# Peripherals.net
KiCad netlist of a schematic drawn in Altium Designer
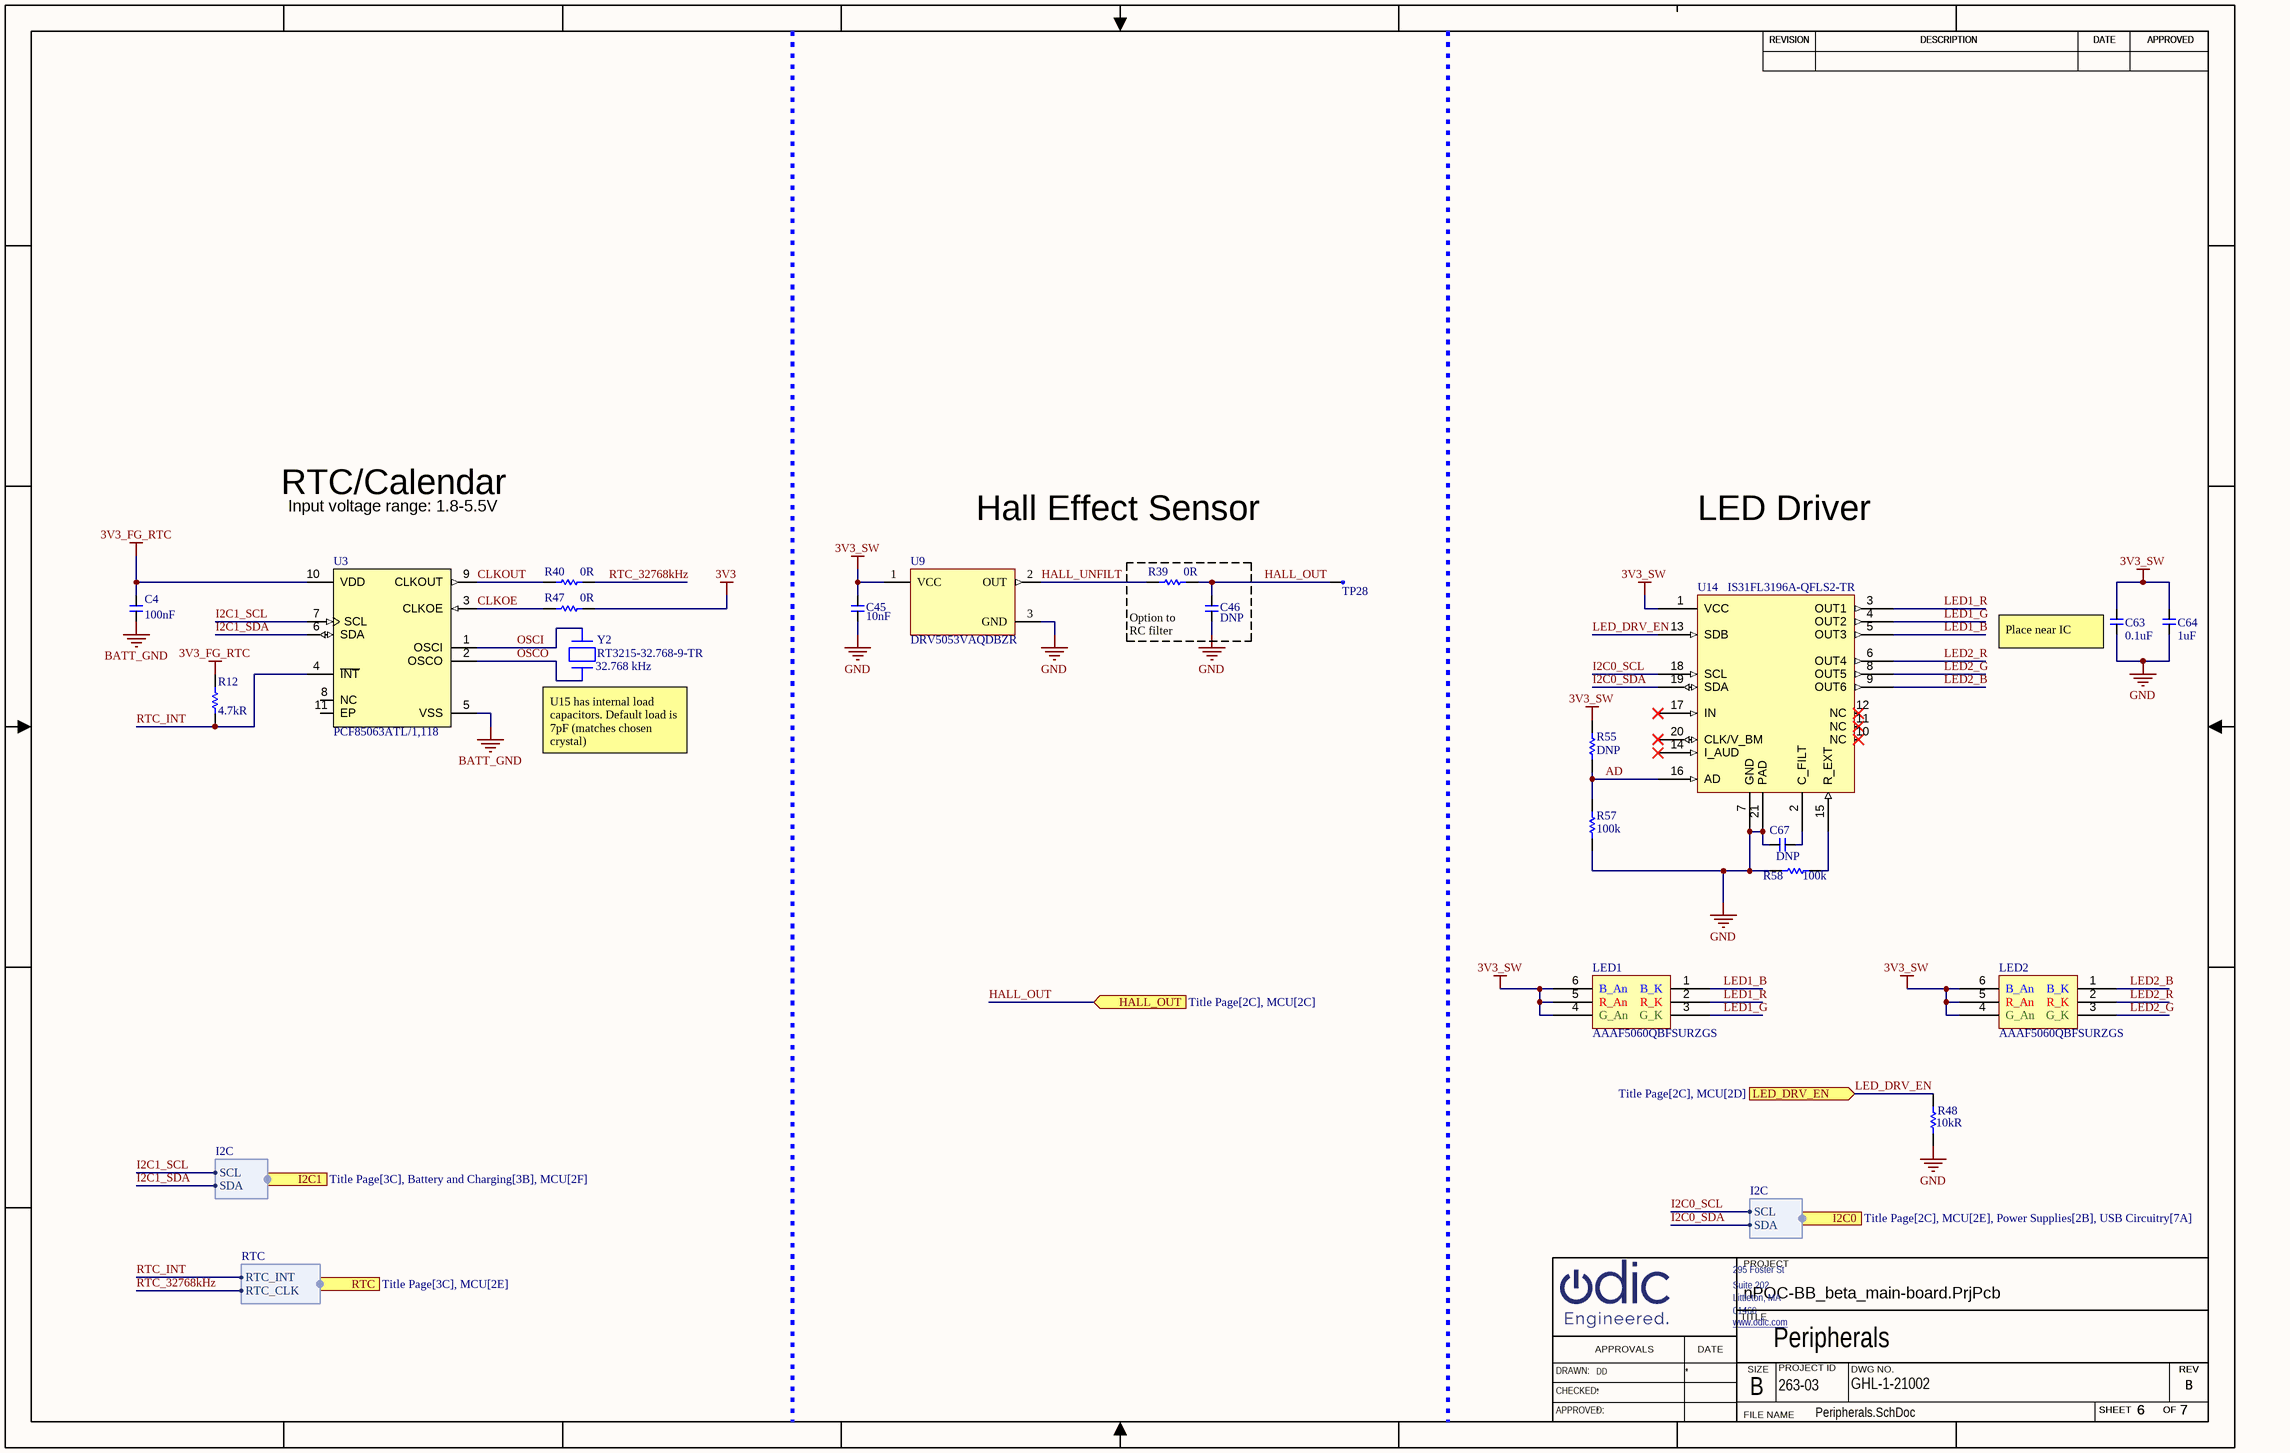
[diagram p0: Peripherals.SchDoc]

(export (version "E")
  (design (tool "Eeschema 10.0.6"))
  (components
    (comp (ref "C4")
      (value "C0402_100n_16V_10pct")
      (footprint "C0402")
      (description "0.1 µF ±10% 16V Ceramic Capacitor X7R 0402 (1005 Metric)")
      (fields
        (field (name "VOLTAGE") "16V")
        (field (name "TOLERANCE") "10%")
        (field (name "CAPACITANCE") "100nF")
      )
      (libsource (lib "Odic Inc") (part "cAP"))
    )
    (comp (ref "C45")
      (value "C0402_10n_6V3_10pct")
      (footprint "C0402")
      (description "CAP CER 10000PF 25V 10% X7R 0402")
      (fields
        (field (name "TOLERANCE") "10%")
        (field (name "CAPACITANCE") "10nF")
        (field (name "VOLTAGE") "25V")
      )
      (libsource (lib "Odic Inc") (part "cAP"))
    )
    (comp (ref "C46")
      (value "C0402 Footprint")
      (footprint "C0402")
      (description "Blank pads for future cap placements")
      (fields (field (name "INSTALL") "DNP"))
      (libsource (lib "Odic Inc") (part "cAP"))
    )
    (comp (ref "C63")
      (value "0.1uF")
      (footprint "C0402")
      (description "Cap Ceramic 0.1uF 25V X5R 10% Pad SMD 0402 Multi Layer Ceramic Capacitor (MLCC)")
      (fields (field (name "VOLTAGE") "25V") (field (name "TOLERANCE") "10%"))
      (libsource (lib "Odic Inc") (part "cAP"))
    )
    (comp (ref "C64")
      (value "1uF")
      (footprint "C0402")
      (description "CAP CER 1UF 16V X5R 0402")
      (fields (field (name "VOLTAGE") "16V") (field (name "TOLERANCE") "10%"))
      (libsource (lib "Odic Inc") (part "cAP"))
    )
    (comp (ref "C67")
      (value "N/A")
      (footprint "C0603")
      (description "DNP CAP")
      (fields
        (field (name "MANUFACTURER") "Samsung")
        (field (name "MANUFACTURER PART NUMBER") "CL10B104KB8NNWC")
        (field (name "INSTALL") "DNP")
      )
      (libsource (lib "Odic Inc") (part "cAP"))
    )
    (comp (ref "LED1")
      (value "AAAF5060QBFSURZGS")
      (footprint "led6_smt_5x6mm")
      (description "Blue/Red/Green 100º 400/800/1000 mcd Clear Surface Mount LED Lamp")
      (libsource (lib "Odic Inc") (part "AAAF5060QBFSURZGS-Symbol-1"))
    )
    (comp (ref "LED2")
      (value "AAAF5060QBFSURZGS")
      (footprint "led6_smt_5x6mm")
      (description "Blue/Red/Green 100º 400/800/1000 mcd Clear Surface Mount LED Lamp")
      (libsource (lib "Odic Inc") (part "AAAF5060QBFSURZGS-Symbol-1"))
    )
    (comp (ref "R12")
      (value "R0402_4k7_1pct")
      (footprint "R0402")
      (description "RES 4.7K OHM 1% 1/16W 0402")
      (fields (field (name "TOLERANCE") "1%") (field (name "RESISTANCE") "4.7kR"))
      (libsource (lib "Odic Inc") (part "RES"))
    )
    (comp (ref "R39")
      (value "R0402_0R")
      (footprint "R0402")
      (description "RES 0 OHM JUMPER 1/16W 0402")
      (fields (field (name "RESISTANCE") "0R"))
      (libsource (lib "Odic Inc") (part "RES"))
    )
    (comp (ref "R40")
      (value "R0402_0R")
      (footprint "R0402")
      (description "RES 0 OHM JUMPER 1/16W 0402")
      (fields (field (name "RESISTANCE") "0R"))
      (libsource (lib "Odic Inc") (part "RES"))
    )
    (comp (ref "R47")
      (value "R0402_0R")
      (footprint "R0402")
      (description "RES 0 OHM JUMPER 1/16W 0402")
      (fields (field (name "RESISTANCE") "0R"))
      (libsource (lib "Odic Inc") (part "RES"))
    )
    (comp (ref "R48")
      (value "R0402_10k_1pct")
      (footprint "R0402")
      (description "Res Thick Film 0402 10K Ohm 1% 1/16W ±100ppm/°C Molded SMD SMD T/R")
      (fields (field (name "RESISTANCE") "10kR") (field (name "TOLERANCE") "1%"))
      (libsource (lib "Odic Inc") (part "RES"))
    )
    (comp (ref "R55")
      (value "DNP")
      (footprint "R0402")
      (description "Unpopulated 0402 pads. No part number associated with this \"component\"")
      (libsource (lib "Odic Inc") (part "RES"))
    )
    (comp (ref "R57")
      (value "100k")
      (footprint "R0402")
      (description "Res General Purpose Thick Film 0402 100K Ohm 1% 1/16W ±100ppm/°C Molded SMD Paper T/R")
      (fields (field (name "TOLERANCE") "1%"))
      (libsource (lib "Odic Inc") (part "RES"))
    )
    (comp (ref "R58")
      (value "100k")
      (footprint "R0402")
      (description "Res General Purpose Thick Film 0402 100K Ohm 1% 1/16W ±100ppm/°C Molded SMD Paper T/R")
      (fields (field (name "TOLERANCE") "1%"))
      (libsource (lib "Odic Inc") (part "RES"))
    )
    (comp (ref "TP28")
      (value "TPC30")
      (footprint "tpc30")
      (description "Test Point Circle 30")
      (libsource (lib "Odic Inc") (part "TPC"))
    )
    (comp (ref "U3")
      (value "PCF85063ATL/1,118")
      (footprint "dfn10_2p6x2p6_p5mm")
      (description "IC RTC CLK/CALENDAR I2C 10-SON")
      (libsource (lib "Odic Inc") (part "PCF85063A"))
    )
    (comp (ref "U9")
      (value "DRV5053VAQDBZR")
      (footprint "SOT23")
      (description "SENSOR HALL ANALOG SOT23-3 / Hall Effect Sensor Single Axis SOT-23-3")
      (libsource (lib "Odic Inc") (part "DRV5053VAQDBZR-symbol"))
    )
    (comp (ref "U14")
      (value "IS31FL3196A-QFLS2-TR")
      (footprint "qfn20_3x3_p4mm")
      (description "6-Channel Light Effect LED Driver with I2C Interface 2.7V to 5.5V Input 20-Pin QFN T/R")
      (libsource (lib "Odic Inc") (part "IS31FL3196A-QFLS2-TR-Symbol-1"))
    )
    (comp (ref "Y2")
      (value "RT3215-32.768-9-TR")
      (footprint "xtal2_3p2x1p5")
      (description "RT3215 Series 0.032768 ±20 ppm 9pF -40°C TO +85°C SMT Tuning Fork Crystal")
      (fields (field (name "OPERATING FREQUENCY") "32.768 kHz"))
      (libsource (lib "Odic Inc") (part "Y*"))
    )
  )
  (nets
    (net (code "3") (name "/AD") (class "Default")
      (node (ref "R55") (pin "1") (pinfunction "1_1") (pintype "passive"))
      (node (ref "R57") (pin "2") (pinfunction "2_2") (pintype "passive"))
      (node (ref "U14") (pin "16") (pinfunction "AD_16") (pintype "input"))
    )
    (net (code "4") (name "/CLKOE") (class "Default")
      (node (ref "R47") (pin "1") (pinfunction "1_1") (pintype "passive"))
      (node (ref "U3") (pin "3") (pinfunction "CLKOE_3") (pintype "input"))
    )
    (net (code "5") (name "/CLKOUT") (class "Default")
      (node (ref "R40") (pin "1") (pinfunction "1_1") (pintype "passive"))
      (node (ref "U3") (pin "9") (pinfunction "CLKOUT_9") (pintype "output"))
    )
    (net (code "6") (name "/HALL_OUT") (class "Default")
      (node (ref "C46") (pin "2") (pinfunction "2_2") (pintype "passive"))
      (node (ref "R39") (pin "2") (pinfunction "2_2") (pintype "passive"))
      (node (ref "TP28") (pin "1") (pinfunction "1_1") (pintype "passive"))
    )
    (net (code "7") (name "/HALL_UNFILT") (class "Default")
      (node (ref "R39") (pin "1") (pinfunction "1_1") (pintype "passive"))
      (node (ref "U9") (pin "2") (pinfunction "OUT_2") (pintype "output"))
    )
    (net (code "8") (name "/I2C0_SCL") (class "Default")
      (node (ref "U14") (pin "18") (pinfunction "SCL_18") (pintype "input"))
    )
    (net (code "9") (name "/I2C0_SDA") (class "Default")
      (node (ref "U14") (pin "19") (pinfunction "SDA_19") (pintype "bidirectional"))
    )
    (net (code "10") (name "/I2C1_SCL") (class "Default")
      (node (ref "U3") (pin "7") (pinfunction "SCL_7") (pintype "input"))
    )
    (net (code "11") (name "/I2C1_SDA") (class "Default")
      (node (ref "U3") (pin "6") (pinfunction "SDA_6") (pintype "bidirectional"))
    )
    (net (code "12") (name "/LED1_B") (class "Default")
      (node (ref "LED1") (pin "1") (pinfunction "B_K_1") (pintype "passive"))
      (node (ref "U14") (pin "5") (pinfunction "OUT3_5") (pintype "output"))
    )
    (net (code "13") (name "/LED1_G") (class "Default")
      (node (ref "LED1") (pin "3") (pinfunction "G_K_3") (pintype "passive"))
      (node (ref "U14") (pin "4") (pinfunction "OUT2_4") (pintype "output"))
    )
    (net (code "14") (name "/LED1_R") (class "Default")
      (node (ref "LED1") (pin "2") (pinfunction "R_K_2") (pintype "passive"))
      (node (ref "U14") (pin "3") (pinfunction "OUT1_3") (pintype "output"))
    )
    (net (code "15") (name "/LED2_B") (class "Default")
      (node (ref "LED2") (pin "1") (pinfunction "B_K_1") (pintype "passive"))
      (node (ref "U14") (pin "9") (pinfunction "OUT6_9") (pintype "output"))
    )
    (net (code "16") (name "/LED2_G") (class "Default")
      (node (ref "LED2") (pin "3") (pinfunction "G_K_3") (pintype "passive"))
      (node (ref "U14") (pin "8") (pinfunction "OUT5_8") (pintype "output"))
    )
    (net (code "17") (name "/LED2_R") (class "Default")
      (node (ref "LED2") (pin "2") (pinfunction "R_K_2") (pintype "passive"))
      (node (ref "U14") (pin "6") (pinfunction "OUT4_6") (pintype "output"))
    )
    (net (code "18") (name "/LED_DRV_EN") (class "Default")
      (node (ref "R48") (pin "1") (pinfunction "1_1") (pintype "passive"))
      (node (ref "U14") (pin "13") (pinfunction "SDB_13") (pintype "input"))
    )
    (net (code "19") (name "/OSCI") (class "Default")
      (node (ref "U3") (pin "1") (pinfunction "OSCI_1") (pintype "passive"))
      (node (ref "Y2") (pin "1") (pinfunction "1_1") (pintype "passive"))
    )
    (net (code "20") (name "/OSCO") (class "Default")
      (node (ref "U3") (pin "2") (pinfunction "OSCO_2") (pintype "passive"))
      (node (ref "Y2") (pin "2") (pinfunction "2_2") (pintype "passive"))
    )
    (net (code "21") (name "/RTC_32768kHz") (class "Default")
      (node (ref "R40") (pin "2") (pinfunction "2_2") (pintype "passive"))
    )
    (net (code "22") (name "/RTC_INT") (class "Default")
      (node (ref "R12") (pin "1") (pinfunction "1_1") (pintype "passive"))
      (node (ref "U3") (pin "4") (pinfunction "~{INT}_4") (pintype "open_collector"))
    )
    (net (code "25") (name "3V3") (class "Default")
      (node (ref "R47") (pin "2") (pinfunction "2_2") (pintype "passive"))
    )
    (net (code "26") (name "3V3_FG_RTC") (class "Default")
      (node (ref "C4") (pin "1") (pinfunction "1_1") (pintype "passive"))
      (node (ref "R12") (pin "2") (pinfunction "2_2") (pintype "passive"))
      (node (ref "U3") (pin "10") (pinfunction "VDD_10") (pintype "power_in"))
    )
    (net (code "27") (name "3V3_SW") (class "Default")
      (node (ref "C45") (pin "2") (pinfunction "2_2") (pintype "passive"))
      (node (ref "C63") (pin "2") (pinfunction "2_2") (pintype "passive"))
      (node (ref "C64") (pin "2") (pinfunction "2_2") (pintype "passive"))
      (node (ref "LED1") (pin "4") (pinfunction "G_An_4") (pintype "passive"))
      (node (ref "LED1") (pin "5") (pinfunction "R_An_5") (pintype "passive"))
      (node (ref "LED1") (pin "6") (pinfunction "B_An_6") (pintype "passive"))
      (node (ref "LED2") (pin "4") (pinfunction "G_An_4") (pintype "passive"))
      (node (ref "LED2") (pin "5") (pinfunction "R_An_5") (pintype "passive"))
      (node (ref "LED2") (pin "6") (pinfunction "B_An_6") (pintype "passive"))
      (node (ref "R55") (pin "2") (pinfunction "2_2") (pintype "passive"))
      (node (ref "U14") (pin "1") (pinfunction "VCC_1") (pintype "power_in"))
      (node (ref "U9") (pin "1") (pinfunction "VCC_1") (pintype "power_in"))
    )
    (net (code "28") (name "BATT_GND") (class "Default")
      (node (ref "C4") (pin "2") (pinfunction "2_2") (pintype "passive"))
      (node (ref "U3") (pin "5") (pinfunction "VSS_5") (pintype "power_in"))
    )
    (net (code "29") (name "GND") (class "Default")
      (node (ref "C45") (pin "1") (pinfunction "1_1") (pintype "passive"))
      (node (ref "C46") (pin "1") (pinfunction "1_1") (pintype "passive"))
      (node (ref "C63") (pin "1") (pinfunction "1_1") (pintype "passive"))
      (node (ref "C64") (pin "1") (pinfunction "1_1") (pintype "passive"))
      (node (ref "C67") (pin "2") (pinfunction "2_2") (pintype "passive"))
      (node (ref "R48") (pin "2") (pinfunction "2_2") (pintype "passive"))
      (node (ref "R57") (pin "1") (pinfunction "1_1") (pintype "passive"))
      (node (ref "R58") (pin "2") (pinfunction "2_2") (pintype "passive"))
      (node (ref "U14") (pin "21") (pinfunction "PAD_21") (pintype "passive"))
      (node (ref "U14") (pin "7") (pinfunction "GND_7") (pintype "passive"))
      (node (ref "U9") (pin "3") (pinfunction "GND_3") (pintype "power_in"))
    )
    (net (code "30") (name "Net-(U14-C_FILT)") (class "Default")
      (node (ref "C67") (pin "1") (pinfunction "1_1") (pintype "passive"))
      (node (ref "U14") (pin "2") (pinfunction "C_FILT_2") (pintype "passive"))
    )
    (net (code "31") (name "Net-(U14-R_EXT)") (class "Default")
      (node (ref "R58") (pin "1") (pinfunction "1_1") (pintype "passive"))
      (node (ref "U14") (pin "15") (pinfunction "R_EXT_15") (pintype "input"))
    )
    (net (code "32") (name "unconnected-(U3-EP-Pad11)") (class "Default")
      (node (ref "U3") (pin "11") (pinfunction "EP_11") (pintype "power_in"))
    )
    (net (code "33") (name "unconnected-(U3-NC-Pad8)") (class "Default")
      (node (ref "U3") (pin "8") (pinfunction "NC_8") (pintype "passive"))
    )
    (net (code "34") (name "unconnected-(U14-CLK{slash}V_BM-Pad20)") (class "Default")
      (node (ref "U14") (pin "20") (pinfunction "CLK/V_BM_20") (pintype "bidirectional+no_connect"))
    )
    (net (code "35") (name "unconnected-(U14-IN-Pad17)") (class "Default")
      (node (ref "U14") (pin "17") (pinfunction "IN_17") (pintype "input+no_connect"))
    )
    (net (code "36") (name "unconnected-(U14-I_AUD-Pad14)") (class "Default")
      (node (ref "U14") (pin "14") (pinfunction "I_AUD_14") (pintype "input+no_connect"))
    )
    (net (code "37") (name "unconnected-(U14-NC-Pad10)") (class "Default")
      (node (ref "U14") (pin "10") (pinfunction "NC_10") (pintype "passive+no_connect"))
    )
    (net (code "38") (name "unconnected-(U14-NC-Pad11)") (class "Default")
      (node (ref "U14") (pin "11") (pinfunction "NC_11") (pintype "passive+no_connect"))
    )
    (net (code "39") (name "unconnected-(U14-NC-Pad12)") (class "Default")
      (node (ref "U14") (pin "12") (pinfunction "NC_12") (pintype "passive+no_connect"))
    )
  )
)
